# 22180210-_-.net
KiCad netlist of a schematic drawn in EasyEDA Pro
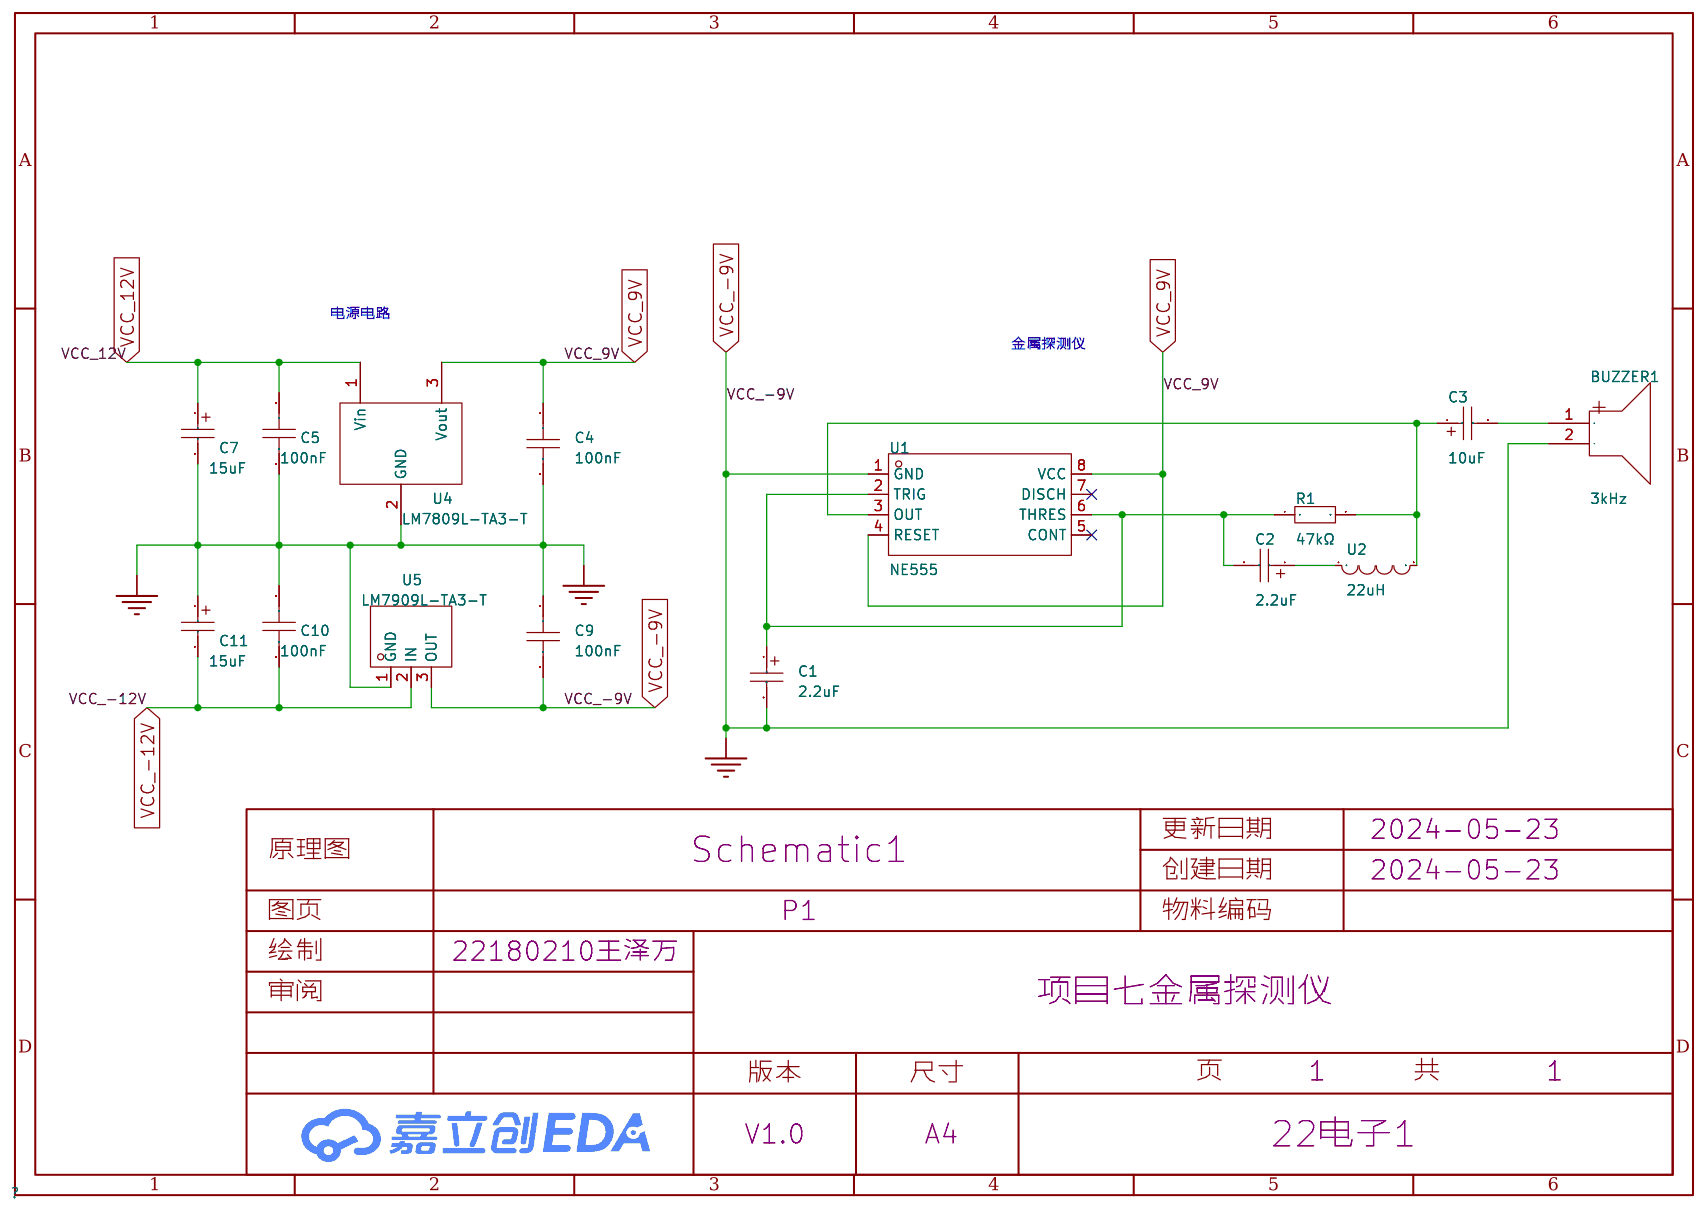
[diagram p0: schematic sheet]

(export (version "E")
  (design (tool "Eeschema 10.0.6"))
  (components
    (comp (ref "BUZZER1")
      (value "3kHz")
      (footprint "easyedapro:BUZ-TH_BD9.0-P5.00-D0.6-FD")
      (description "驱动方式:有源(内含驱动线路);构造类型:电磁式;频率:3kHz;声压(SPL):85dB@10cm;")
      (fields (field (name "Manufacturer Part") "HNB09A03") (field (name "Manufacturer") "华能"))
      (libsource (lib "easyedapro") (part "HNB09A03"))
    )
    (comp (ref "C1")
      (value "2.2uF")
      (footprint "easyedapro:C_Ele_SMD_3x5.4mm")
      (libsource (lib "easyedapro") (part "CAP"))
    )
    (comp (ref "C2")
      (value "2.2uF")
      (footprint "easyedapro:C_Ele_SMD_3x5.4mm")
      (libsource (lib "easyedapro") (part "CAP"))
    )
    (comp (ref "C3")
      (value "10uF")
      (footprint "easyedapro:C_Ele_SMD_3x5.4mm")
      (libsource (lib "easyedapro") (part "CAP"))
    )
    (comp (ref "C4")
      (value "100nF")
      (footprint "easyedapro:C0603")
      (description "容值:100nF;精度:±10%;额定电压:50V;材质(温度系数):X7R;")
      (fields (field (name "Manufacturer Part") "C0603X104K050T") (field (name "Manufacturer") "IHHEC(禾伸堂)"))
      (libsource (lib "easyedapro") (part "C0603X104K050T"))
    )
    (comp (ref "C5")
      (value "100nF")
      (footprint "easyedapro:C0603")
      (description "容值:100nF;精度:±10%;额定电压:50V;材质(温度系数):X7R;")
      (fields (field (name "Manufacturer Part") "C0603X104K050T") (field (name "Manufacturer") "IHHEC(禾伸堂)"))
      (libsource (lib "easyedapro") (part "C0603X104K050T"))
    )
    (comp (ref "C7")
      (value "15uF")
      (footprint "easyedapro:C_Ele_SMD_3x5.4mm")
      (libsource (lib "easyedapro") (part "CAP"))
    )
    (comp (ref "C9")
      (value "100nF")
      (footprint "easyedapro:C0603")
      (description "容值:100nF;精度:±10%;额定电压:50V;材质(温度系数):X7R;")
      (fields (field (name "Manufacturer Part") "C0603X104K050T") (field (name "Manufacturer") "IHHEC(禾伸堂)"))
      (libsource (lib "easyedapro") (part "C0603X104K050T"))
    )
    (comp (ref "C10")
      (value "100nF")
      (footprint "easyedapro:C0603")
      (description "容值:100nF;精度:±10%;额定电压:50V;材质(温度系数):X7R;")
      (fields (field (name "Manufacturer Part") "C0603X104K050T") (field (name "Manufacturer") "IHHEC(禾伸堂)"))
      (libsource (lib "easyedapro") (part "C0603X104K050T"))
    )
    (comp (ref "C11")
      (value "15uF")
      (footprint "easyedapro:C_Ele_SMD_3x5.4mm")
      (libsource (lib "easyedapro") (part "CAP"))
    )
    (comp (ref "R1")
      (value "47kΩ")
      (footprint "easyedapro:R0603")
      (description "电阻类型:厚膜电阻;阻值:47kΩ;精度:±1%;功率:100mW;最大工作电压:75V;温度系数:±100ppm/°C;")
      (fields
        (field (name "Manufacturer Part") "0603WAF4702T5E")
        (field (name "Manufacturer") "UNI-ROYAL(厚声)")
      )
      (libsource (lib "easyedapro") (part "0603WAF4702T5E"))
    )
    (comp (ref "U1")
      (value "NE555")
      (footprint "easyedapro:SOP-8_L5.0-W4.0-P1.27-LS6.0-BL")
      (libsource (lib "easyedapro") (part "NE555"))
    )
    (comp (ref "U2")
      (value "22uH")
      (footprint "easyedapro:IND-TH_L16.5-W8.5-P11.00-D1.0")
      (description "电感值:22uH;精度:±20%;额定电流:5A;饱和电流(Isat):-;类型:磁环电感;Q值:-;")
      (fields
        (field (name "Manufacturer Part") "SLT050125T220MUB")
        (field (name "Manufacturer") "Sunltech(韩国顺磁)")
      )
      (libsource (lib "easyedapro") (part "SLT050125T220MUB"))
    )
    (comp (ref "U4")
      (value "LM7809L-TA3-T")
      (footprint "easyedapro:TO-220-3_L10.0-W4.5-P2.54-L")
      (description "输出类型:固定;最大输入电压:35V;输出电压:9V;最大输出电流:1A;输出极性:正极;")
      (fields (field (name "Manufacturer") "UTC(友顺)"))
      (libsource (lib "easyedapro") (part "LM7809L-TA3-T"))
    )
    (comp (ref "U5")
      (value "LM7909L-TA3-T")
      (footprint "easyedapro:TO-220-3_L10.0-W4.5-P2.54-L")
      (description "输出类型:固定;最大输入电压:26V;输出电压:9V;最大输出电流:1A;电源纹波抑制比(PSRR):60dB@(120Hz);输出极性:负极;")
      (fields (field (name "Manufacturer") "UTC(友顺)"))
      (libsource (lib "easyedapro") (part "LM7909L-TA3-T"))
    )
  )
  (nets
    (net (code "1") (name "GND") (class "Default")
      (node (ref "C10") (pin "1") (pinfunction "1_1") (pintype "unspecified"))
      (node (ref "C11") (pin "1") (pinfunction "1_1") (pintype "input"))
      (node (ref "C4") (pin "2") (pinfunction "2_2") (pintype "unspecified"))
      (node (ref "C5") (pin "2") (pinfunction "2_2") (pintype "unspecified"))
      (node (ref "C7") (pin "2") (pinfunction "2_2") (pintype "input"))
      (node (ref "C9") (pin "1") (pinfunction "1_1") (pintype "unspecified"))
      (node (ref "U4") (pin "2") (pinfunction "GND_2") (pintype "input"))
      (node (ref "U5") (pin "1") (pinfunction "GND_1") (pintype "input"))
    )
    (net (code "2") (name "Net-(BUZZER1-+)") (class "Default")
      (node (ref "BUZZER1") (pin "1") (pinfunction "+_1") (pintype "unspecified"))
      (node (ref "C3") (pin "2") (pinfunction "2_2") (pintype "input"))
    )
    (net (code "3") (name "Net-(C2-Pad1)") (class "Default")
      (node (ref "C2") (pin "1") (pinfunction "1_1") (pintype "input"))
      (node (ref "U2") (pin "1") (pinfunction "1_1") (pintype "unspecified"))
    )
    (net (code "4") (name "Net-(U1-OUT)") (class "Default")
      (node (ref "C3") (pin "1") (pinfunction "1_1") (pintype "input"))
      (node (ref "R1") (pin "2") (pinfunction "2_2") (pintype "input"))
      (node (ref "U1") (pin "3") (pinfunction "OUT_3") (pintype "unspecified"))
      (node (ref "U2") (pin "2") (pinfunction "2_2") (pintype "unspecified"))
    )
    (net (code "5") (name "Net-(U1-THRES)") (class "Default")
      (node (ref "C1") (pin "1") (pinfunction "1_1") (pintype "input"))
      (node (ref "C2") (pin "2") (pinfunction "2_2") (pintype "input"))
      (node (ref "R1") (pin "1") (pinfunction "1_1") (pintype "input"))
      (node (ref "U1") (pin "2") (pinfunction "TRIG_2") (pintype "unspecified"))
      (node (ref "U1") (pin "6") (pinfunction "THRES_6") (pintype "unspecified"))
    )
    (net (code "6") (name "VCC_-9V") (class "Default")
      (node (ref "BUZZER1") (pin "2") (pinfunction "-_2") (pintype "unspecified"))
      (node (ref "C1") (pin "2") (pinfunction "2_2") (pintype "input"))
      (node (ref "C9") (pin "2") (pinfunction "2_2") (pintype "unspecified"))
      (node (ref "U1") (pin "1") (pinfunction "GND_1") (pintype "unspecified"))
      (node (ref "U5") (pin "3") (pinfunction "OUT_3") (pintype "input"))
    )
    (net (code "7") (name "VCC_-12V") (class "Default")
      (node (ref "C10") (pin "2") (pinfunction "2_2") (pintype "unspecified"))
      (node (ref "C11") (pin "2") (pinfunction "2_2") (pintype "input"))
      (node (ref "U5") (pin "2") (pinfunction "IN_2") (pintype "input"))
    )
    (net (code "8") (name "VCC_9V") (class "Default")
      (node (ref "C4") (pin "1") (pinfunction "1_1") (pintype "unspecified"))
      (node (ref "U1") (pin "4") (pinfunction "RESET_4") (pintype "unspecified"))
      (node (ref "U1") (pin "8") (pinfunction "VCC_8") (pintype "unspecified"))
      (node (ref "U4") (pin "3") (pinfunction "Vout_3") (pintype "input"))
    )
    (net (code "9") (name "VCC_12V") (class "Default")
      (node (ref "C5") (pin "1") (pinfunction "1_1") (pintype "unspecified"))
      (node (ref "C7") (pin "1") (pinfunction "1_1") (pintype "input"))
      (node (ref "U4") (pin "1") (pinfunction "Vin_1") (pintype "input"))
    )
    (net (code "10") (name "unconnected-(U1-CONT-Pad5)") (class "Default")
      (node (ref "U1") (pin "5") (pinfunction "CONT_5") (pintype "unspecified+no_connect"))
    )
    (net (code "11") (name "unconnected-(U1-DISCH-Pad7)") (class "Default")
      (node (ref "U1") (pin "7") (pinfunction "DISCH_7") (pintype "unspecified+no_connect"))
    )
  )
)
